# Power.net
KiCad netlist of a schematic drawn in Altium Designer
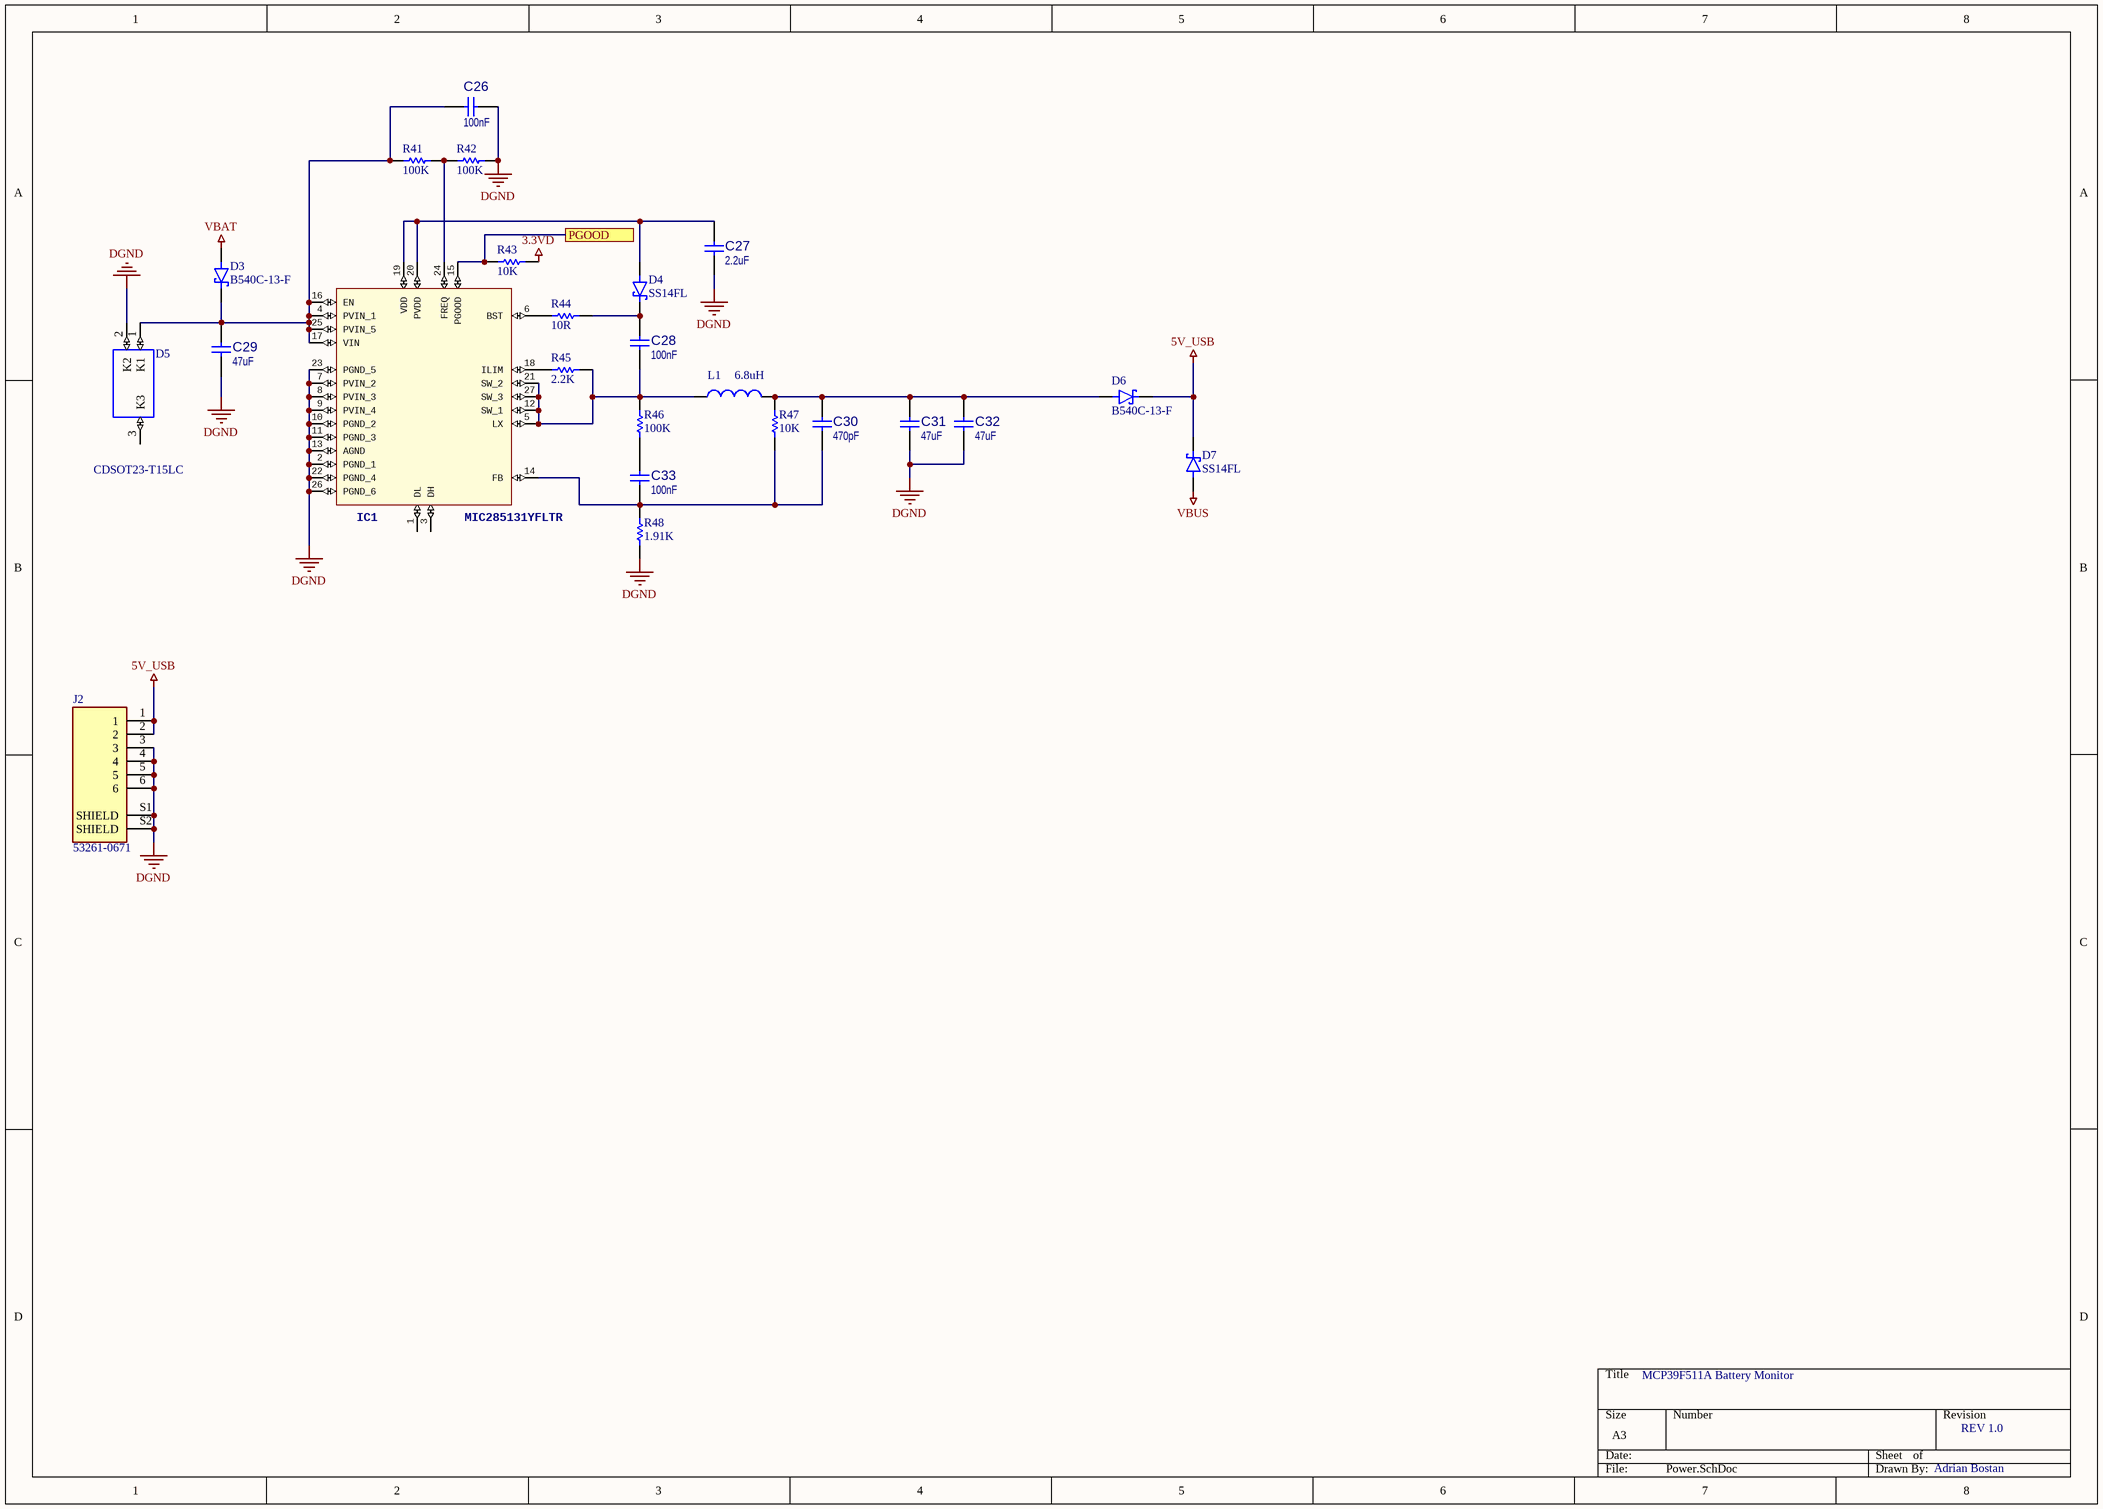
[diagram p0: Power.SchDoc]

(export (version "E")
  (design (tool "Eeschema 10.0.6"))
  (components
    (comp (ref "C26")
      (value "100nF")
      (footprint "CAP0603M")
      (description "Capacitor")
      (fields (field (name "TOLERANCE") "10%") (field (name "OWNER") "Aaron VanDuerm"))
      (libsource (lib "MCHP-CDB") (part "Capacitor NP"))
    )
    (comp (ref "C27")
      (value "2.2uF")
      (footprint "CAP0603M")
      (description "Capacitor")
      (fields (field (name "TOLERANCE") "10%") (field (name "OWNER") "Aaron VanDuerm"))
      (libsource (lib "MCHP-CDB") (part "Capacitor NP"))
    )
    (comp (ref "C28")
      (value "100nF")
      (footprint "CAP0603M")
      (description "Capacitor")
      (fields (field (name "TOLERANCE") "10%") (field (name "OWNER") "Aaron VanDuerm"))
      (libsource (lib "MCHP-CDB") (part "Capacitor NP"))
    )
    (comp (ref "C29")
      (value "47uF")
      (footprint "Tantal D")
      (description "Capacitor")
      (fields (field (name "TOLERANCE") "10%") (field (name "OWNER") "Aaron VanDuerm"))
      (libsource (lib "MCHP-CDB") (part "Capacitor NP"))
    )
    (comp (ref "C30")
      (value "470pF")
      (footprint "CAP0603M")
      (description "Capacitor")
      (fields (field (name "TOLERANCE") "10%") (field (name "OWNER") "Aaron VanDuerm"))
      (libsource (lib "MCHP-CDB") (part "Capacitor NP"))
    )
    (comp (ref "C31")
      (value "47uF")
      (footprint "Tantal D")
      (description "Capacitor")
      (fields (field (name "TOLERANCE") "10%") (field (name "OWNER") "Aaron VanDuerm"))
      (libsource (lib "MCHP-CDB") (part "Capacitor NP"))
    )
    (comp (ref "C32")
      (value "47uF")
      (footprint "Tantal D")
      (description "Capacitor")
      (fields (field (name "TOLERANCE") "10%") (field (name "OWNER") "Aaron VanDuerm"))
      (libsource (lib "MCHP-CDB") (part "Capacitor NP"))
    )
    (comp (ref "C33")
      (value "100nF")
      (footprint "CAP0603M")
      (description "Capacitor")
      (fields (field (name "TOLERANCE") "10%") (field (name "OWNER") "Aaron VanDuerm"))
      (libsource (lib "MCHP-CDB") (part "Capacitor NP"))
    )
    (comp (ref "D3")
      (value "B540C-13-F")
      (footprint "B540C-13-F")
      (description "Diode Schottky 40V 5A Surface Mount SMC")
      (fields (field (name "MF") "Multicomp"))
      (libsource (lib "B540C-13") (part "B540C-13-F"))
    )
    (comp (ref "D4")
      (value "SS14FL")
      (footprint "SODFL3617X108N")
      (description "Diode Schottky 40V 1A Surface Mount SOD-123F")
      (fields (field (name "DIGI-KEY_PART_NUMBER") "SS14FLCT-ND") (field (name "MF") "ON Semiconductor"))
      (libsource (lib "SS14FL") (part "SS14FL"))
    )
    (comp (ref "D5")
      (value "CDSOT23-T15LC")
      (footprint "SOT95P230X117-3N")
      (description "40V Clamp 8A _8/20Âµs_ Ipp Tvs Diode Surface Mount SOT-23")
      (fields (field (name "MP") "CDSOT23-T24CAN") (field (name "MF") "Bourns"))
      (libsource (lib "CDSOT23-T24CAN") (part "CDSOT23-T24CAN"))
    )
    (comp (ref "D6")
      (value "B540C-13-F")
      (footprint "B540C-13-F")
      (description "Diode Schottky 40V 5A Surface Mount SMC")
      (fields (field (name "MF") "Multicomp"))
      (libsource (lib "B540C-13") (part "B540C-13-F"))
    )
    (comp (ref "D7")
      (value "SS14FL")
      (footprint "SODFL3617X108N")
      (description "Diode Schottky 40V 1A Surface Mount SOD-123F")
      (fields (field (name "DIGI-KEY_PART_NUMBER") "SS14FLCT-ND") (field (name "MF") "ON Semiconductor"))
      (libsource (lib "SS14FL") (part "SS14FL"))
    )
    (comp (ref "IC1")
      (value "MIC285131YFLTR")
      (footprint "MIC285131YFLTR")
      (fields
        (field (name "MANUFACTURER_PART_NUMBER") "MIC28513-1YFL-TR")
        (field (name "MOUSER_PART_NUMBER") "998-MIC28513-1YFLTR")
      )
      (libsource (lib "MIC28513-1YFL-TR") (part "MIC28513-1YFL-TR"))
    )
    (comp (ref "J2")
      (value "53261-0671")
      (footprint "53261-0671")
      (description "Picoblade Connector, 6 Circuit Single Row, Right Angle Surface Mount SMT PCB")
      (fields (field (name "MP") "0532610671") (field (name "DIGI-KEY_PART_NUMBER") "WM7624CT-ND"))
      (libsource (lib "53261-0671") (part "53261-0671"))
    )
    (comp (ref "L1")
      (value "6.8uH")
      (footprint "SRR1050A-6R8Y")
      (description "Inductor")
      (fields (field (name "Comment") "SRR1050A-6R8Y") (field (name "PUBLISHER") "Altium Limited"))
      (libsource (lib "Miscellaneous Devices") (part "Inductor"))
    )
    (comp (ref "R41")
      (value "100K")
      (footprint "RES0603M")
      (description "Resistor")
      (fields (field (name "Comment") "Res1") (field (name "PUBLISHER") "Altium Limited"))
      (libsource (lib "Miscellaneous Devices") (part "Res1"))
    )
    (comp (ref "R42")
      (value "100K")
      (footprint "RES0603M")
      (description "Resistor")
      (fields (field (name "Comment") "Res1") (field (name "PUBLISHER") "Altium Limited"))
      (libsource (lib "Miscellaneous Devices") (part "Res1"))
    )
    (comp (ref "R43")
      (value "10K")
      (footprint "RES0603M")
      (description "Resistor")
      (fields (field (name "Comment") "Res1") (field (name "PUBLISHER") "Altium Limited"))
      (libsource (lib "Miscellaneous Devices") (part "Res1"))
    )
    (comp (ref "R44")
      (value "10R")
      (footprint "RES0603M")
      (description "Resistor")
      (fields (field (name "Comment") "Res1") (field (name "PUBLISHER") "Altium Limited"))
      (libsource (lib "Miscellaneous Devices") (part "Res1"))
    )
    (comp (ref "R45")
      (value "2.2K")
      (footprint "RES0603M")
      (description "Resistor")
      (fields (field (name "Comment") "Res1") (field (name "PUBLISHER") "Altium Limited"))
      (libsource (lib "Miscellaneous Devices") (part "Res1"))
    )
    (comp (ref "R46")
      (value "100K")
      (footprint "RES0603M")
      (description "Resistor")
      (fields (field (name "Comment") "Res1") (field (name "PUBLISHER") "Altium Limited"))
      (libsource (lib "Miscellaneous Devices") (part "Res1"))
    )
    (comp (ref "R47")
      (value "10K")
      (footprint "RES0603M")
      (description "Resistor")
      (fields (field (name "Comment") "Res1") (field (name "PUBLISHER") "Altium Limited"))
      (libsource (lib "Miscellaneous Devices") (part "Res1"))
    )
    (comp (ref "R48")
      (value "1.91K")
      (footprint "RES0603M")
      (description "Resistor")
      (fields (field (name "Comment") "Res1") (field (name "PUBLISHER") "Altium Limited"))
      (libsource (lib "Miscellaneous Devices") (part "Res1"))
    )
  )
  (nets
    (net (code "1") (name "/PGOOD") (class "Default")
      (node (ref "IC1") (pin "15") (pinfunction "PGOOD_15") (pintype "bidirectional"))
      (node (ref "R43") (pin "2") (pinfunction "2_2") (pintype "passive"))
    )
    (net (code "2") (name "3.3VD") (class "Default")
      (node (ref "R43") (pin "1") (pinfunction "1_1") (pintype "passive"))
    )
    (net (code "3") (name "5V_USB") (class "Default")
      (node (ref "D6") (pin "C") (pinfunction "K_C") (pintype "passive"))
      (node (ref "D7") (pin "C") (pinfunction "K_C") (pintype "passive"))
      (node (ref "J2") (pin "1") (pinfunction "1_1") (pintype "passive"))
      (node (ref "J2") (pin "2") (pinfunction "2_2") (pintype "passive"))
    )
    (net (code "4") (name "DGND") (class "Default")
      (node (ref "C26") (pin "1") (pinfunction "1_1") (pintype "passive"))
      (node (ref "C27") (pin "1") (pinfunction "1_1") (pintype "passive"))
      (node (ref "C29") (pin "1") (pinfunction "1_1") (pintype "passive"))
      (node (ref "C31") (pin "1") (pinfunction "1_1") (pintype "passive"))
      (node (ref "C32") (pin "1") (pinfunction "1_1") (pintype "passive"))
      (node (ref "D5") (pin "2") (pinfunction "K2_2") (pintype "bidirectional"))
      (node (ref "IC1") (pin "10") (pinfunction "PGND_2_10") (pintype "bidirectional"))
      (node (ref "IC1") (pin "11") (pinfunction "PGND_3_11") (pintype "bidirectional"))
      (node (ref "IC1") (pin "13") (pinfunction "AGND_13") (pintype "bidirectional"))
      (node (ref "IC1") (pin "2") (pinfunction "PGND_1_2") (pintype "bidirectional"))
      (node (ref "IC1") (pin "22") (pinfunction "PGND_4_22") (pintype "bidirectional"))
      (node (ref "IC1") (pin "23") (pinfunction "PGND_5_23") (pintype "bidirectional"))
      (node (ref "IC1") (pin "26") (pinfunction "PGND_6_26") (pintype "bidirectional"))
      (node (ref "IC1") (pin "7") (pinfunction "PVIN_2_7") (pintype "bidirectional"))
      (node (ref "IC1") (pin "8") (pinfunction "PVIN_3_8") (pintype "bidirectional"))
      (node (ref "IC1") (pin "9") (pinfunction "PVIN_4_9") (pintype "bidirectional"))
      (node (ref "J2") (pin "3") (pinfunction "3_3") (pintype "passive"))
      (node (ref "J2") (pin "4") (pinfunction "4_4") (pintype "passive"))
      (node (ref "J2") (pin "5") (pinfunction "5_5") (pintype "passive"))
      (node (ref "J2") (pin "6") (pinfunction "6_6") (pintype "passive"))
      (node (ref "J2") (pin "S1") (pinfunction "SHIELD_S1") (pintype "passive"))
      (node (ref "J2") (pin "S2") (pinfunction "SHIELD_S2") (pintype "passive"))
      (node (ref "R42") (pin "1") (pinfunction "1_1") (pintype "passive"))
      (node (ref "R48") (pin "2") (pinfunction "2_2") (pintype "passive"))
    )
    (net (code "5") (name "Net-(C30-Pad2)") (class "Default")
      (node (ref "C30") (pin "2") (pinfunction "2_2") (pintype "passive"))
      (node (ref "C31") (pin "2") (pinfunction "2_2") (pintype "passive"))
      (node (ref "C32") (pin "2") (pinfunction "2_2") (pintype "passive"))
      (node (ref "D6") (pin "A") (pinfunction "A_A") (pintype "passive"))
      (node (ref "L1") (pin "2") (pinfunction "2_2") (pintype "passive"))
      (node (ref "R47") (pin "1") (pinfunction "1_1") (pintype "passive"))
    )
    (net (code "6") (name "Net-(C33-Pad2)") (class "Default")
      (node (ref "C33") (pin "2") (pinfunction "2_2") (pintype "passive"))
      (node (ref "R46") (pin "2") (pinfunction "2_2") (pintype "passive"))
    )
    (net (code "7") (name "Net-(D3-K)") (class "Default")
      (node (ref "C26") (pin "2") (pinfunction "2_2") (pintype "passive"))
      (node (ref "C29") (pin "2") (pinfunction "2_2") (pintype "passive"))
      (node (ref "D3") (pin "C") (pinfunction "K_C") (pintype "passive"))
      (node (ref "D5") (pin "1") (pinfunction "K1_1") (pintype "bidirectional"))
      (node (ref "IC1") (pin "16") (pinfunction "EN_16") (pintype "bidirectional"))
      (node (ref "IC1") (pin "17") (pinfunction "VIN_17") (pintype "bidirectional"))
      (node (ref "IC1") (pin "25") (pinfunction "PVIN_5_25") (pintype "bidirectional"))
      (node (ref "IC1") (pin "4") (pinfunction "PVIN_1_4") (pintype "bidirectional"))
      (node (ref "R41") (pin "2") (pinfunction "2_2") (pintype "passive"))
    )
    (net (code "8") (name "Net-(D4-K)") (class "Default")
      (node (ref "C28") (pin "2") (pinfunction "2_2") (pintype "passive"))
      (node (ref "D4") (pin "C") (pinfunction "K_C") (pintype "passive"))
      (node (ref "R44") (pin "1") (pinfunction "1_1") (pintype "passive"))
    )
    (net (code "9") (name "Net-(IC1-BST)") (class "Default")
      (node (ref "IC1") (pin "6") (pinfunction "BST_6") (pintype "bidirectional"))
      (node (ref "R44") (pin "2") (pinfunction "2_2") (pintype "passive"))
    )
    (net (code "10") (name "Net-(IC1-FB)") (class "Default")
      (node (ref "C30") (pin "1") (pinfunction "1_1") (pintype "passive"))
      (node (ref "C33") (pin "1") (pinfunction "1_1") (pintype "passive"))
      (node (ref "IC1") (pin "14") (pinfunction "FB_14") (pintype "bidirectional"))
      (node (ref "R47") (pin "2") (pinfunction "2_2") (pintype "passive"))
      (node (ref "R48") (pin "1") (pinfunction "1_1") (pintype "passive"))
    )
    (net (code "11") (name "Net-(IC1-FREQ)") (class "Default")
      (node (ref "IC1") (pin "24") (pinfunction "FREQ_24") (pintype "bidirectional"))
      (node (ref "R41") (pin "1") (pinfunction "1_1") (pintype "passive"))
      (node (ref "R42") (pin "2") (pinfunction "2_2") (pintype "passive"))
    )
    (net (code "12") (name "Net-(IC1-ILIM)") (class "Default")
      (node (ref "IC1") (pin "18") (pinfunction "ILIM_18") (pintype "bidirectional"))
      (node (ref "R45") (pin "2") (pinfunction "2_2") (pintype "passive"))
    )
    (net (code "13") (name "Net-(IC1-LX)") (class "Default")
      (node (ref "C28") (pin "1") (pinfunction "1_1") (pintype "passive"))
      (node (ref "IC1") (pin "12") (pinfunction "SW_1_12") (pintype "bidirectional"))
      (node (ref "IC1") (pin "21") (pinfunction "SW_2_21") (pintype "bidirectional"))
      (node (ref "IC1") (pin "27") (pinfunction "SW_3_27") (pintype "bidirectional"))
      (node (ref "IC1") (pin "5") (pinfunction "LX_5") (pintype "bidirectional"))
      (node (ref "L1") (pin "1") (pinfunction "1_1") (pintype "passive"))
      (node (ref "R45") (pin "1") (pinfunction "1_1") (pintype "passive"))
      (node (ref "R46") (pin "1") (pinfunction "1_1") (pintype "passive"))
    )
    (net (code "14") (name "Net-(IC1-PVDD)") (class "Default")
      (node (ref "C27") (pin "2") (pinfunction "2_2") (pintype "passive"))
      (node (ref "D4") (pin "A") (pinfunction "A_A") (pintype "passive"))
      (node (ref "IC1") (pin "19") (pinfunction "VDD_19") (pintype "bidirectional"))
      (node (ref "IC1") (pin "20") (pinfunction "PVDD_20") (pintype "bidirectional"))
    )
    (net (code "15") (name "VBAT") (class "Default")
      (node (ref "D3") (pin "A") (pinfunction "A_A") (pintype "passive"))
    )
    (net (code "16") (name "VBUS") (class "Default")
      (node (ref "D7") (pin "A") (pinfunction "A_A") (pintype "passive"))
    )
    (net (code "17") (name "unconnected-(D5-K3-Pad3)") (class "Default")
      (node (ref "D5") (pin "3") (pinfunction "K3_3") (pintype "bidirectional"))
    )
    (net (code "18") (name "unconnected-(IC1-DH-Pad3)") (class "Default")
      (node (ref "IC1") (pin "3") (pinfunction "DH_3") (pintype "bidirectional"))
    )
    (net (code "19") (name "unconnected-(IC1-DL-Pad1)") (class "Default")
      (node (ref "IC1") (pin "1") (pinfunction "DL_1") (pintype "bidirectional"))
    )
  )
)
